# powerBoard_v4.net
KiCad netlist of a schematic drawn in EAGLE
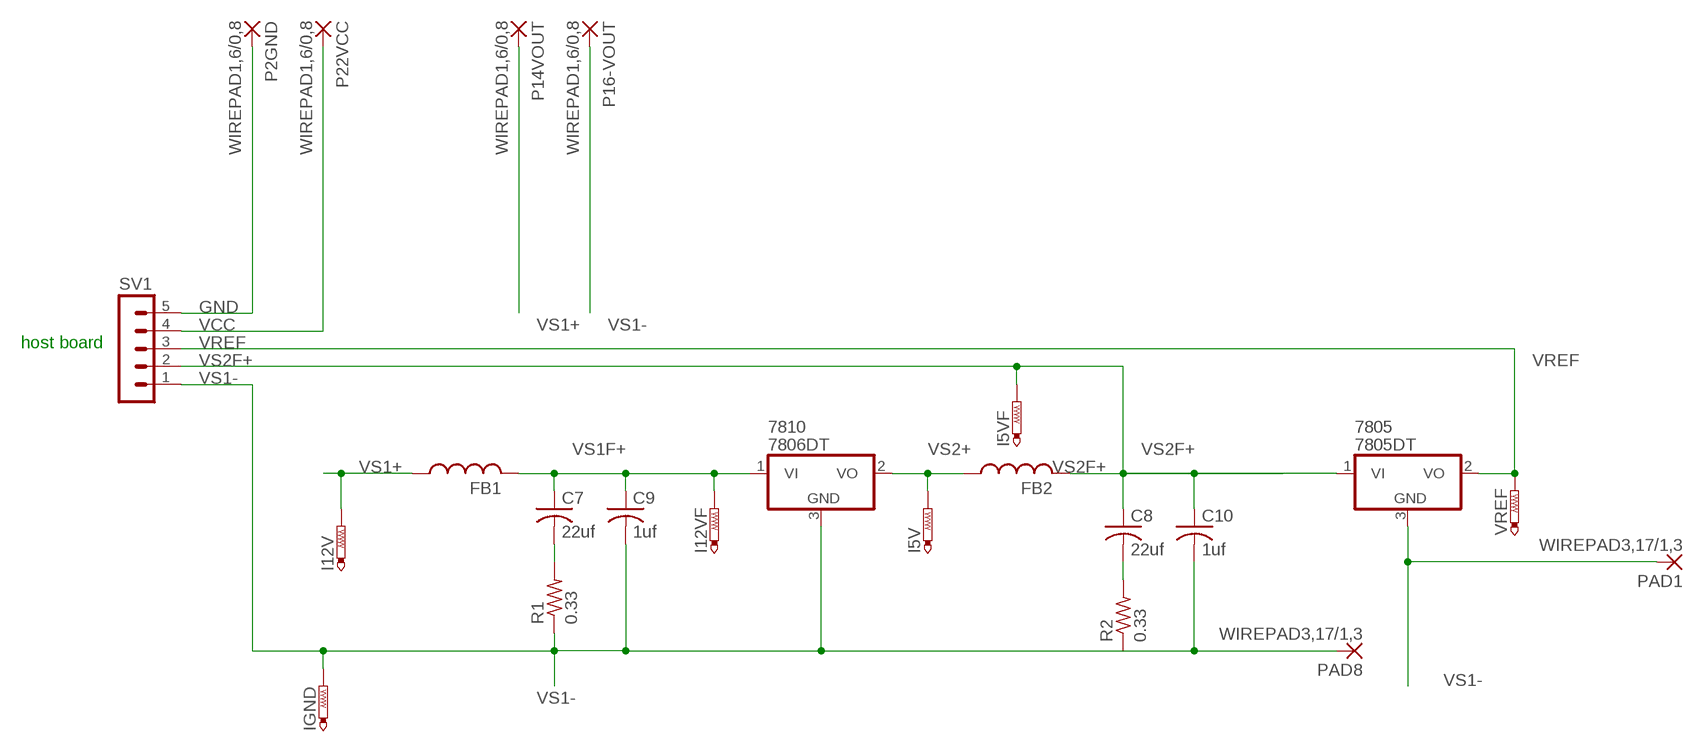
[diagram p0: schematic, sheet 1]

(export (version "E")
  (design (tool "Eeschema 10.0.6"))
  (components
    (comp (ref "7805")
      (value "7805DT")
      (footprint "eagle-import:TO252")
      (libsource (lib "eagle-import") (part "78DT05"))
    )
    (comp (ref "7810")
      (value "7806DT")
      (footprint "eagle-import:TO252")
      (libsource (lib "eagle-import") (part "78DT06"))
    )
    (comp (ref "C7")
      (value "22uf")
      (footprint "eagle-import:C0805K")
      (libsource (lib "eagle-import") (part "C-USC0805K"))
    )
    (comp (ref "C8")
      (value "22uf")
      (footprint "eagle-import:C0805K")
      (libsource (lib "eagle-import") (part "C-USC0805K"))
    )
    (comp (ref "C9")
      (value "1uf")
      (footprint "eagle-import:C0805K")
      (libsource (lib "eagle-import") (part "C-USC0805K"))
    )
    (comp (ref "C10")
      (value "1uf")
      (footprint "eagle-import:C0805K")
      (libsource (lib "eagle-import") (part "C-USC0805K"))
    )
    (comp (ref "FB1")
      (value "L-USL2012C")
      (footprint "eagle-import:L2012C")
      (libsource (lib "eagle-import") (part "L-USL2012C"))
    )
    (comp (ref "FB2")
      (value "L-USL2012C")
      (footprint "eagle-import:L2012C")
      (libsource (lib "eagle-import") (part "L-USL2012C"))
    )
    (comp (ref "I5V")
      (value "PTR1PAD1-13")
      (footprint "eagle-import:P1-13")
      (libsource (lib "eagle-import") (part "PTR1PAD1-13"))
    )
    (comp (ref "I5VF")
      (value "PTR1PAD1-13")
      (footprint "eagle-import:P1-13")
      (libsource (lib "eagle-import") (part "PTR1PAD1-13"))
    )
    (comp (ref "I12V")
      (value "PTR1PAD1-13")
      (footprint "eagle-import:P1-13")
      (libsource (lib "eagle-import") (part "PTR1PAD1-13"))
    )
    (comp (ref "I12VF")
      (value "PTR1PAD1-13")
      (footprint "eagle-import:P1-13")
      (libsource (lib "eagle-import") (part "PTR1PAD1-13"))
    )
    (comp (ref "IGND")
      (value "PTR1PAD1-13")
      (footprint "eagle-import:P1-13")
      (libsource (lib "eagle-import") (part "PTR1PAD1-13"))
    )
    (comp (ref "P2GND")
      (value "WIREPAD1,6/0,8")
      (footprint "eagle-import:1,6_0,8")
      (libsource (lib "eagle-import") (part "WIREPAD1,6/0,8"))
    )
    (comp (ref "P14VOUT")
      (value "WIREPAD1,6/0,8")
      (footprint "eagle-import:1,6_0,8")
      (libsource (lib "eagle-import") (part "WIREPAD1,6/0,8"))
    )
    (comp (ref "P16-VOUT")
      (value "WIREPAD1,6/0,8")
      (footprint "eagle-import:1,6_0,8")
      (libsource (lib "eagle-import") (part "WIREPAD1,6/0,8"))
    )
    (comp (ref "P22VCC")
      (value "WIREPAD1,6/0,8")
      (footprint "eagle-import:1,6_0,8")
      (libsource (lib "eagle-import") (part "WIREPAD1,6/0,8"))
    )
    (comp (ref "PAD1")
      (value "WIREPAD3,17/1,3")
      (footprint "eagle-import:3,17_1,3")
      (libsource (lib "eagle-import") (part "WIREPAD3,17/1,3"))
    )
    (comp (ref "PAD8")
      (value "WIREPAD3,17/1,3")
      (footprint "eagle-import:3,17_1,3")
      (libsource (lib "eagle-import") (part "WIREPAD3,17/1,3"))
    )
    (comp (ref "R1")
      (value "0.33")
      (footprint "eagle-import:R2012W")
      (libsource (lib "eagle-import") (part "R-US_R2012W"))
    )
    (comp (ref "R2")
      (value "0.33")
      (footprint "eagle-import:R2012W")
      (libsource (lib "eagle-import") (part "R-US_R2012W"))
    )
    (comp (ref "SV1")
      (value "MA05-1")
      (footprint "eagle-import:MA05-1")
      (libsource (lib "eagle-import") (part "MA05-1"))
    )
    (comp (ref "VREF")
      (value "PTR1PAD1-13")
      (footprint "eagle-import:P1-13")
      (libsource (lib "eagle-import") (part "PTR1PAD1-13"))
    )
  )
  (nets
    (net (code "1") (name "/GND") (class "Default")
      (node (ref "P2GND") (pin "1") (pinfunction "P_1") (pintype "passive"))
      (node (ref "SV1") (pin "5") (pinfunction "5_5") (pintype "passive"))
    )
    (net (code "2") (name "/VCC") (class "Default")
      (node (ref "P22VCC") (pin "1") (pinfunction "P_1") (pintype "passive"))
      (node (ref "SV1") (pin "4") (pinfunction "4_4") (pintype "passive"))
    )
    (net (code "3") (name "/VREF") (class "Default")
      (node (ref "7805") (pin "2") (pinfunction "VO_2") (pintype "passive"))
      (node (ref "SV1") (pin "3") (pinfunction "3_3") (pintype "passive"))
      (node (ref "VREF") (pin "TP") (pinfunction "TP_TP") (pintype "input"))
    )
    (net (code "4") (name "/VS1+") (class "Default")
      (node (ref "FB1") (pin "1") (pinfunction "1_1") (pintype "passive"))
      (node (ref "I12V") (pin "TP") (pinfunction "TP_TP") (pintype "input"))
      (node (ref "P14VOUT") (pin "1") (pinfunction "P_1") (pintype "passive"))
    )
    (net (code "5") (name "/VS1-") (class "Default")
      (node (ref "7805") (pin "3") (pinfunction "GND_3") (pintype "passive"))
      (node (ref "7810") (pin "3") (pinfunction "GND_3") (pintype "passive"))
      (node (ref "C10") (pin "2") (pinfunction "2_2") (pintype "passive"))
      (node (ref "C9") (pin "2") (pinfunction "2_2") (pintype "passive"))
      (node (ref "IGND") (pin "TP") (pinfunction "TP_TP") (pintype "input"))
      (node (ref "P16-VOUT") (pin "1") (pinfunction "P_1") (pintype "passive"))
      (node (ref "PAD1") (pin "1") (pinfunction "P_1") (pintype "passive"))
      (node (ref "PAD8") (pin "1") (pinfunction "P_1") (pintype "passive"))
      (node (ref "R1") (pin "1") (pinfunction "1_1") (pintype "passive"))
      (node (ref "SV1") (pin "1") (pinfunction "1_1") (pintype "passive"))
    )
    (net (code "6") (name "/VS1F+") (class "Default")
      (node (ref "7810") (pin "1") (pinfunction "VI_1") (pintype "input"))
      (node (ref "C7") (pin "1") (pinfunction "1_1") (pintype "passive"))
      (node (ref "C9") (pin "1") (pinfunction "1_1") (pintype "passive"))
      (node (ref "FB1") (pin "2") (pinfunction "2_2") (pintype "passive"))
      (node (ref "I12VF") (pin "TP") (pinfunction "TP_TP") (pintype "input"))
    )
    (net (code "7") (name "/VS2+") (class "Default")
      (node (ref "7810") (pin "2") (pinfunction "VO_2") (pintype "passive"))
      (node (ref "FB2") (pin "1") (pinfunction "1_1") (pintype "passive"))
      (node (ref "I5V") (pin "TP") (pinfunction "TP_TP") (pintype "input"))
    )
    (net (code "8") (name "/VS2F+") (class "Default")
      (node (ref "7805") (pin "1") (pinfunction "VI_1") (pintype "input"))
      (node (ref "C10") (pin "1") (pinfunction "1_1") (pintype "passive"))
      (node (ref "C8") (pin "1") (pinfunction "1_1") (pintype "passive"))
      (node (ref "FB2") (pin "2") (pinfunction "2_2") (pintype "passive"))
      (node (ref "I5VF") (pin "TP") (pinfunction "TP_TP") (pintype "input"))
      (node (ref "SV1") (pin "2") (pinfunction "2_2") (pintype "passive"))
    )
    (net (code "9") (name "Net-(C7-Pad2)") (class "Default")
      (node (ref "C7") (pin "2") (pinfunction "2_2") (pintype "passive"))
      (node (ref "R1") (pin "2") (pinfunction "2_2") (pintype "passive"))
    )
    (net (code "10") (name "Net-(C8-Pad2)") (class "Default")
      (node (ref "C8") (pin "2") (pinfunction "2_2") (pintype "passive"))
      (node (ref "R2") (pin "2") (pinfunction "2_2") (pintype "passive"))
    )
    (net (code "11") (name "unconnected-(R2-Pad1)") (class "Default")
      (node (ref "R2") (pin "1") (pinfunction "1_1") (pintype "passive"))
    )
  )
)
